# StepperDriver.net
KiCad netlist of a schematic drawn in EAGLE
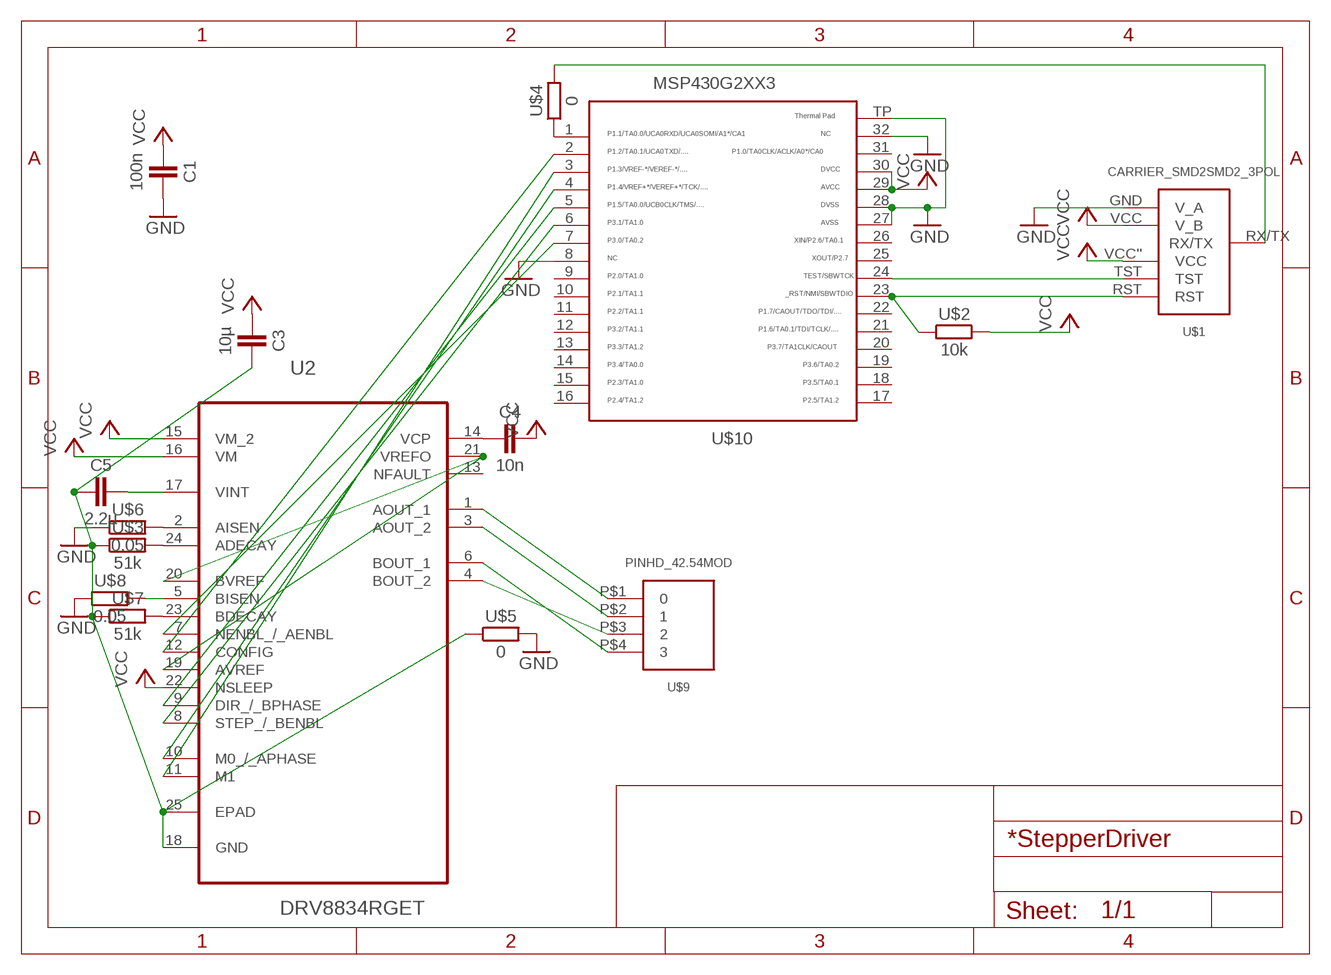
[diagram p0: schematic, sheet 1]

(export (version "E")
  (design (tool "Eeschema 10.0.6"))
  (components
    (comp (ref "C1")
      (value "100n")
      (footprint "eagle-import:603")
      (libsource (lib "eagle-import") (part "CAPACITOR"))
    )
    (comp (ref "C3")
      (value "10µ")
      (footprint "eagle-import:603")
      (libsource (lib "eagle-import") (part "CAPACITOR"))
    )
    (comp (ref "C4")
      (value "10n")
      (footprint "eagle-import:603")
      (libsource (lib "eagle-import") (part "CAPACITOR"))
    )
    (comp (ref "C5")
      (value "2.2µ")
      (footprint "eagle-import:603")
      (libsource (lib "eagle-import") (part "CAPACITOR"))
    )
    (comp (ref "U$1")
      (value "CARRIER_SMD2SMD2_3POL")
      (footprint "eagle-import:CARRIER_SMD2_3POL")
      (libsource (lib "eagle-import") (part "CARRIER_SMD2SMD2_3POL"))
    )
    (comp (ref "U$2")
      (value "10k")
      (footprint "eagle-import:603")
      (libsource (lib "eagle-import") (part "RESISTOR0603"))
    )
    (comp (ref "U$3")
      (value "51k")
      (footprint "eagle-import:603")
      (libsource (lib "eagle-import") (part "RESISTOR0603"))
    )
    (comp (ref "U$4")
      (value "0")
      (footprint "eagle-import:603")
      (libsource (lib "eagle-import") (part "RESISTOR0603"))
    )
    (comp (ref "U$5")
      (value "0")
      (footprint "eagle-import:603")
      (libsource (lib "eagle-import") (part "RESISTOR0603"))
    )
    (comp (ref "U$6")
      (value "0.05")
      (footprint "eagle-import:603")
      (libsource (lib "eagle-import") (part "RESISTOR0603"))
    )
    (comp (ref "U$7")
      (value "51k")
      (footprint "eagle-import:603")
      (libsource (lib "eagle-import") (part "RESISTOR0603"))
    )
    (comp (ref "U$8")
      (value "0.05")
      (footprint "eagle-import:603")
      (libsource (lib "eagle-import") (part "RESISTOR0603"))
    )
    (comp (ref "U$9")
      (value "PINHD_42.54MOD")
      (footprint "eagle-import:PINHD_4_MOD")
      (libsource (lib "eagle-import") (part "PINHD_42.54MOD"))
    )
    (comp (ref "U$10")
      (value "MSP430G2553")
      (footprint "eagle-import:QFN32")
      (libsource (lib "eagle-import") (part "MSP430G2553"))
    )
    (comp (ref "U2")
      (value "DRV8834RGET")
      (footprint "eagle-import:QFN50P400X400X100-25N")
      (libsource (lib "eagle-import") (part "DRV8834RGET"))
    )
  )
  (nets
    (net (code "1") (name "GND") (class "Default")
      (node (ref "C1") (pin "2") (pinfunction "2_2") (pintype "passive"))
      (node (ref "U$1") (pin "GND") (pinfunction "V_A_GND") (pintype "bidirectional"))
      (node (ref "U$10") (pin "27") (pinfunction "27_27") (pintype "bidirectional"))
      (node (ref "U$10") (pin "28") (pinfunction "28_28") (pintype "bidirectional"))
      (node (ref "U$10") (pin "32") (pinfunction "32_32") (pintype "bidirectional"))
      (node (ref "U$10") (pin "8") (pinfunction "8_8") (pintype "bidirectional"))
      (node (ref "U$10") (pin "TP") (pinfunction "TP_TP") (pintype "bidirectional"))
      (node (ref "U$5") (pin "2") (pinfunction "2_2") (pintype "passive"))
      (node (ref "U$6") (pin "1") (pinfunction "1_1") (pintype "passive"))
      (node (ref "U$8") (pin "1") (pinfunction "1_1") (pintype "passive"))
    )
    (net (code "2") (name "Net-(U$1-PadRST)") (class "Default")
      (node (ref "U$1") (pin "RST") (pinfunction "RST_RST") (pintype "bidirectional"))
      (node (ref "U$10") (pin "23") (pinfunction "23_23") (pintype "bidirectional"))
      (node (ref "U$2") (pin "1") (pinfunction "1_1") (pintype "passive"))
    )
    (net (code "3") (name "Net-(U$1-PadRX{slash}TX)") (class "Default")
      (node (ref "U$1") (pin "RX/TX") (pinfunction "RX/TX_RX/TX") (pintype "bidirectional"))
      (node (ref "U$4") (pin "2") (pinfunction "2_2") (pintype "passive"))
    )
    (net (code "4") (name "Net-(U$1-PadTST)") (class "Default")
      (node (ref "U$1") (pin "TST") (pinfunction "TST_TST") (pintype "bidirectional"))
      (node (ref "U$10") (pin "24") (pinfunction "24_24") (pintype "bidirectional"))
    )
    (net (code "5") (name "Net-(U$9-0)") (class "Default")
      (node (ref "U$9") (pin "P$1") (pinfunction "0_P$1") (pintype "bidirectional"))
      (node (ref "U2") (pin "1") (pinfunction "AOUT_1_1") (pintype "output"))
    )
    (net (code "6") (name "Net-(U$9-1)") (class "Default")
      (node (ref "U$9") (pin "P$2") (pinfunction "1_P$2") (pintype "bidirectional"))
      (node (ref "U2") (pin "3") (pinfunction "AOUT_2_3") (pintype "output"))
    )
    (net (code "7") (name "Net-(U$9-2)") (class "Default")
      (node (ref "U$9") (pin "P$3") (pinfunction "2_P$3") (pintype "bidirectional"))
      (node (ref "U2") (pin "4") (pinfunction "BOUT_2_4") (pintype "output"))
    )
    (net (code "8") (name "Net-(U$9-3)") (class "Default")
      (node (ref "U$9") (pin "P$4") (pinfunction "3_P$4") (pintype "bidirectional"))
      (node (ref "U2") (pin "6") (pinfunction "BOUT_1_6") (pintype "output"))
    )
    (net (code "9") (name "Net-(U$10-Pad1)") (class "Default")
      (node (ref "U$10") (pin "1") (pinfunction "1_1") (pintype "bidirectional"))
      (node (ref "U$4") (pin "1") (pinfunction "1_1") (pintype "passive"))
    )
    (net (code "10") (name "Net-(U2-ADECAY)") (class "Default")
      (node (ref "U$3") (pin "2") (pinfunction "2_2") (pintype "passive"))
      (node (ref "U2") (pin "24") (pinfunction "ADECAY_24") (pintype "input"))
    )
    (net (code "11") (name "Net-(U2-AISEN)") (class "Default")
      (node (ref "U$6") (pin "2") (pinfunction "2_2") (pintype "passive"))
      (node (ref "U2") (pin "2") (pinfunction "AISEN_2") (pintype "bidirectional"))
    )
    (net (code "12") (name "Net-(U2-AVREF)") (class "Default")
      (node (ref "U2") (pin "19") (pinfunction "AVREF_19") (pintype "input"))
      (node (ref "U2") (pin "20") (pinfunction "BVREF_20") (pintype "input"))
      (node (ref "U2") (pin "21") (pinfunction "VREFO_21") (pintype "output"))
    )
    (net (code "13") (name "Net-(U2-BDECAY)") (class "Default")
      (node (ref "U$7") (pin "2") (pinfunction "2_2") (pintype "passive"))
      (node (ref "U2") (pin "23") (pinfunction "BDECAY_23") (pintype "input"))
    )
    (net (code "14") (name "Net-(U2-BISEN)") (class "Default")
      (node (ref "U$8") (pin "2") (pinfunction "2_2") (pintype "passive"))
      (node (ref "U2") (pin "5") (pinfunction "BISEN_5") (pintype "bidirectional"))
    )
    (net (code "15") (name "Net-(U2-CONFIG)") (class "Default")
      (node (ref "U$10") (pin "2") (pinfunction "2_2") (pintype "bidirectional"))
      (node (ref "U2") (pin "12") (pinfunction "CONFIG_12") (pintype "input"))
    )
    (net (code "16") (name "Net-(U2-DIR_{slash}_BPHASE)") (class "Default")
      (node (ref "U$10") (pin "5") (pinfunction "5_5") (pintype "bidirectional"))
      (node (ref "U2") (pin "9") (pinfunction "DIR_/_BPHASE_9") (pintype "input"))
    )
    (net (code "17") (name "Net-(U2-EPAD)") (class "Default")
      (node (ref "C3") (pin "2") (pinfunction "2_2") (pintype "passive"))
      (node (ref "C5") (pin "1") (pinfunction "1_1") (pintype "passive"))
      (node (ref "U$3") (pin "1") (pinfunction "1_1") (pintype "passive"))
      (node (ref "U$5") (pin "1") (pinfunction "1_1") (pintype "passive"))
      (node (ref "U$7") (pin "1") (pinfunction "1_1") (pintype "passive"))
      (node (ref "U2") (pin "18") (pinfunction "GND_18") (pintype "passive"))
      (node (ref "U2") (pin "25") (pinfunction "EPAD_25") (pintype "passive"))
    )
    (net (code "18") (name "Net-(U2-M0_{slash}_APHASE)") (class "Default")
      (node (ref "U$10") (pin "4") (pinfunction "4_4") (pintype "bidirectional"))
      (node (ref "U2") (pin "10") (pinfunction "M0_/_APHASE_10") (pintype "input"))
    )
    (net (code "19") (name "Net-(U2-M1)") (class "Default")
      (node (ref "U$10") (pin "3") (pinfunction "3_3") (pintype "bidirectional"))
      (node (ref "U2") (pin "11") (pinfunction "M1_11") (pintype "input"))
    )
    (net (code "20") (name "Net-(U2-NENBL_{slash}_AENBL)") (class "Default")
      (node (ref "U$10") (pin "7") (pinfunction "7_7") (pintype "bidirectional"))
      (node (ref "U2") (pin "7") (pinfunction "NENBL_/_AENBL_7") (pintype "input"))
    )
    (net (code "21") (name "Net-(U2-STEP_{slash}_BENBL)") (class "Default")
      (node (ref "U$10") (pin "6") (pinfunction "6_6") (pintype "bidirectional"))
      (node (ref "U2") (pin "8") (pinfunction "STEP_/_BENBL_8") (pintype "input"))
    )
    (net (code "22") (name "Net-(U2-VCP)") (class "Default")
      (node (ref "C4") (pin "1") (pinfunction "1_1") (pintype "passive"))
      (node (ref "U2") (pin "14") (pinfunction "VCP_14") (pintype "output"))
    )
    (net (code "23") (name "Net-(U2-VINT)") (class "Default")
      (node (ref "C5") (pin "2") (pinfunction "2_2") (pintype "passive"))
      (node (ref "U2") (pin "17") (pinfunction "VINT_17") (pintype "power_in"))
    )
    (net (code "24") (name "VCC") (class "Default")
      (node (ref "C1") (pin "1") (pinfunction "1_1") (pintype "passive"))
      (node (ref "C3") (pin "1") (pinfunction "1_1") (pintype "passive"))
      (node (ref "C4") (pin "2") (pinfunction "2_2") (pintype "passive"))
      (node (ref "U$1") (pin "VCC") (pinfunction "V_B_VCC") (pintype "bidirectional"))
      (node (ref "U$1") (pin "VCC''") (pinfunction "VCC_VCC''") (pintype "bidirectional"))
      (node (ref "U$10") (pin "29") (pinfunction "29_29") (pintype "bidirectional"))
      (node (ref "U$10") (pin "30") (pinfunction "30_30") (pintype "bidirectional"))
      (node (ref "U$2") (pin "2") (pinfunction "2_2") (pintype "passive"))
      (node (ref "U2") (pin "15") (pinfunction "VM_2_15") (pintype "power_in"))
      (node (ref "U2") (pin "16") (pinfunction "VM_16") (pintype "power_in"))
      (node (ref "U2") (pin "22") (pinfunction "NSLEEP_22") (pintype "input"))
    )
    (net (code "25") (name "unconnected-(U$10-Pad9)") (class "Default")
      (node (ref "U$10") (pin "9") (pinfunction "9_9") (pintype "bidirectional"))
    )
    (net (code "26") (name "unconnected-(U$10-Pad10)") (class "Default")
      (node (ref "U$10") (pin "10") (pinfunction "10_10") (pintype "bidirectional"))
    )
    (net (code "27") (name "unconnected-(U$10-Pad11)") (class "Default")
      (node (ref "U$10") (pin "11") (pinfunction "11_11") (pintype "bidirectional"))
    )
    (net (code "28") (name "unconnected-(U$10-Pad12)") (class "Default")
      (node (ref "U$10") (pin "12") (pinfunction "12_12") (pintype "bidirectional"))
    )
    (net (code "29") (name "unconnected-(U$10-Pad13)") (class "Default")
      (node (ref "U$10") (pin "13") (pinfunction "13_13") (pintype "bidirectional"))
    )
    (net (code "30") (name "unconnected-(U$10-Pad14)") (class "Default")
      (node (ref "U$10") (pin "14") (pinfunction "14_14") (pintype "bidirectional"))
    )
    (net (code "31") (name "unconnected-(U$10-Pad15)") (class "Default")
      (node (ref "U$10") (pin "15") (pinfunction "15_15") (pintype "bidirectional"))
    )
    (net (code "32") (name "unconnected-(U$10-Pad16)") (class "Default")
      (node (ref "U$10") (pin "16") (pinfunction "16_16") (pintype "bidirectional"))
    )
    (net (code "33") (name "unconnected-(U$10-Pad17)") (class "Default")
      (node (ref "U$10") (pin "17") (pinfunction "17_17") (pintype "bidirectional"))
    )
    (net (code "34") (name "unconnected-(U$10-Pad18)") (class "Default")
      (node (ref "U$10") (pin "18") (pinfunction "18_18") (pintype "bidirectional"))
    )
    (net (code "35") (name "unconnected-(U$10-Pad19)") (class "Default")
      (node (ref "U$10") (pin "19") (pinfunction "19_19") (pintype "bidirectional"))
    )
    (net (code "36") (name "unconnected-(U$10-Pad20)") (class "Default")
      (node (ref "U$10") (pin "20") (pinfunction "20_20") (pintype "bidirectional"))
    )
    (net (code "37") (name "unconnected-(U$10-Pad21)") (class "Default")
      (node (ref "U$10") (pin "21") (pinfunction "21_21") (pintype "bidirectional"))
    )
    (net (code "38") (name "unconnected-(U$10-Pad22)") (class "Default")
      (node (ref "U$10") (pin "22") (pinfunction "22_22") (pintype "bidirectional"))
    )
    (net (code "39") (name "unconnected-(U$10-Pad25)") (class "Default")
      (node (ref "U$10") (pin "25") (pinfunction "25_25") (pintype "bidirectional"))
    )
    (net (code "40") (name "unconnected-(U$10-Pad26)") (class "Default")
      (node (ref "U$10") (pin "26") (pinfunction "26_26") (pintype "bidirectional"))
    )
    (net (code "41") (name "unconnected-(U$10-Pad31)") (class "Default")
      (node (ref "U$10") (pin "31") (pinfunction "31_31") (pintype "bidirectional"))
    )
    (net (code "42") (name "unconnected-(U2-NFAULT-Pad13)") (class "Default")
      (node (ref "U2") (pin "13") (pinfunction "NFAULT_13") (pintype "output"))
    )
  )
)
